# MCU.net
KiCad netlist of a schematic drawn in Altium Designer
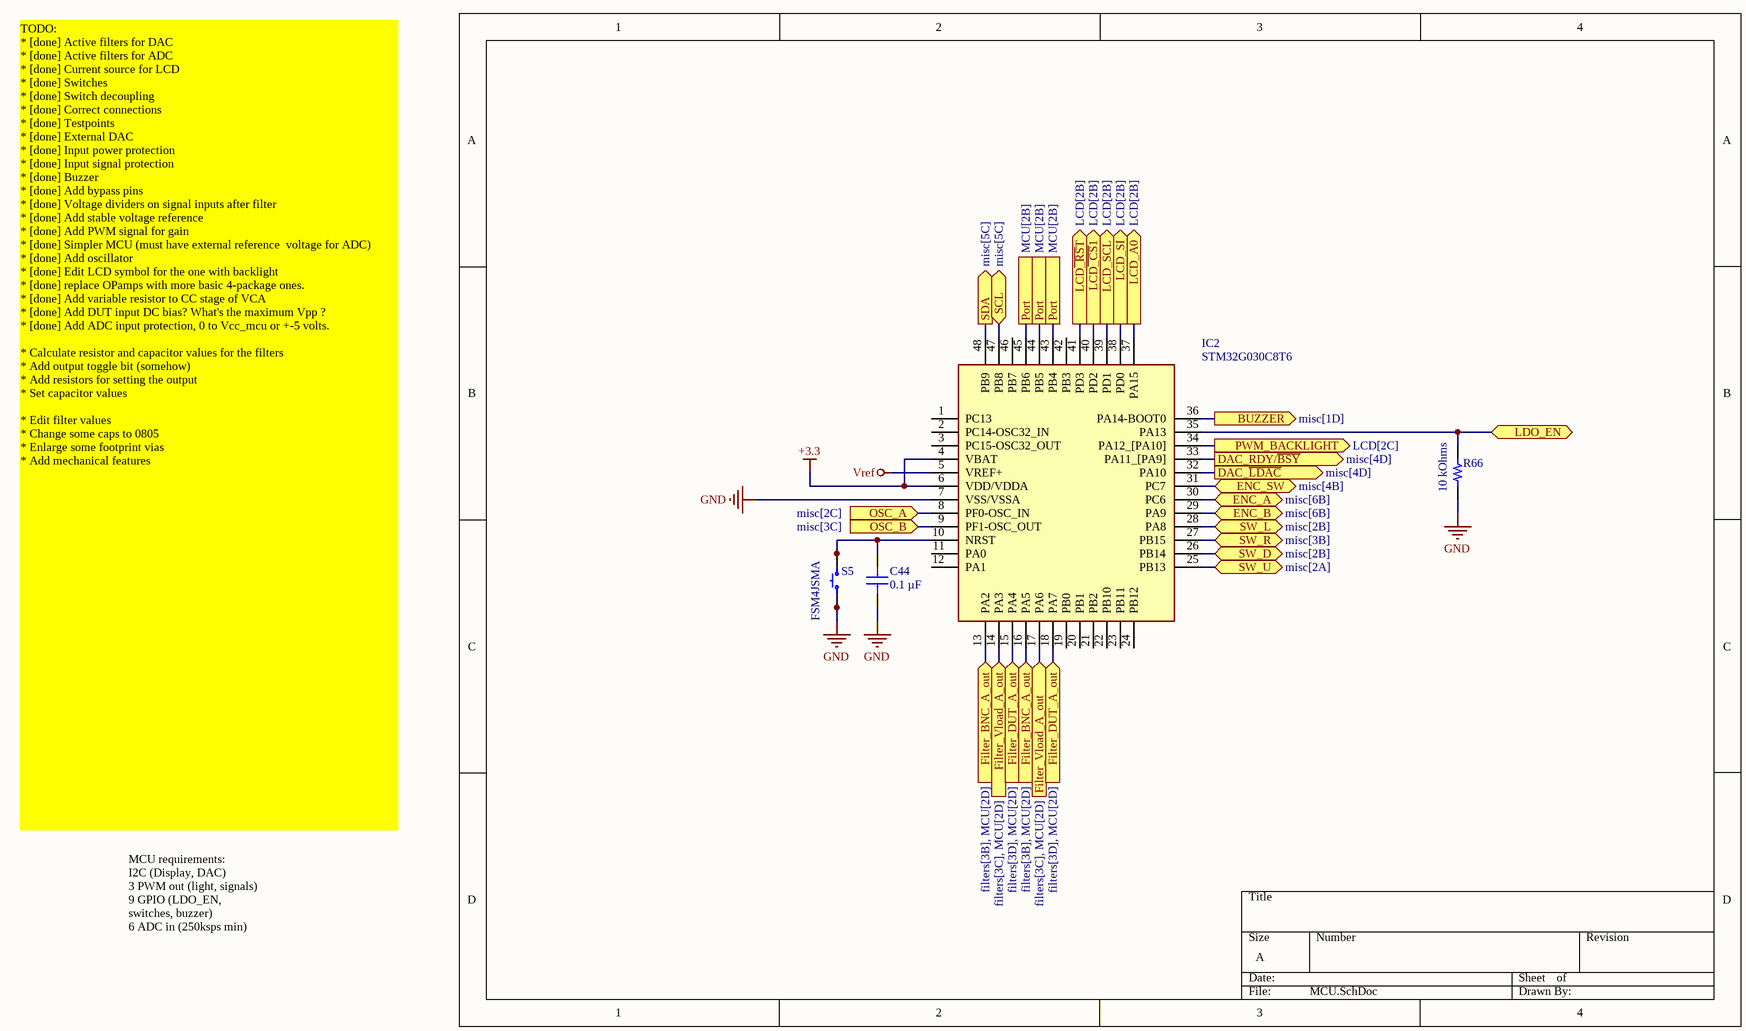
[diagram p0: MCU.SchDoc]

(export (version "E")
  (design (tool "Eeschema 10.0.6"))
  (components
    (comp (ref "C44")
      (value "0.1 µF")
      (footprint "CAP 1206_3216 - 0.8MM")
      (description "CAP CER 0.1UF 50V X7R 1206")
      (fields
        (field (name "PART NUMBER") "885012208087")
        (field (name "CAPACITANCE") "0.1 µF")
        (field (name "MANUFACTURER") "Würth Elektronik")
      )
      (libsource (lib "Celestial Altium Library - altium_library") (part "Capacitor"))
    )
    (comp (ref "IC2")
      (value "STM32G030C8T6")
      (footprint "QFP50P900X900X160-48N")
      (description "Integrated Circuit")
      (fields (field (name "MOUSER PART NUMBER") "511-STM32G030C8T6"))
      (libsource (lib "za_koncar") (part "STM32G030C8T6"))
    )
    (comp (ref "R66")
      (value "10 kOhms")
      (footprint "YAGEO RES 1206_3216")
      (description "RES SMD 10K OHM 1% 1/4W 1206")
      (fields (field (name "PART NUMBER") "RT1206FRE0710KL") (field (name "MANUFACTURER") "Yageo"))
      (libsource (lib "Celestial Altium Library - altium_library") (part "Resistor"))
    )
    (comp (ref "S5")
      (value "FSM4JSMA")
      (footprint "TE FSM4JSMA")
      (description "SWITCH TACTILE SPST-NO 0.05A 24V")
      (fields (field (name "MANUFACTURER") "TE Connectivity ALCOSWITCH Switches"))
      (libsource (lib "Celestial Altium Library - altium_library") (part "SPST-NO 4 PIN"))
    )
  )
  (nets
    (net (code "1") (name "+3.3") (class "Default")
      (node (ref "IC2") (pin "4") (pinfunction "VBAT_4") (pintype "passive"))
      (node (ref "IC2") (pin "6") (pinfunction "VDD/VDDA_6") (pintype "passive"))
    )
    (net (code "2") (name "/BUZZER") (class "Default")
      (node (ref "IC2") (pin "36") (pinfunction "PA14-BOOT0_36") (pintype "passive"))
    )
    (net (code "3") (name "/DAC_RDY{slash}~{BSY}") (class "Default")
      (node (ref "IC2") (pin "33") (pinfunction "PA11_[PA9]_33") (pintype "passive"))
    )
    (net (code "4") (name "/DAC_~{LDAC}") (class "Default")
      (node (ref "IC2") (pin "32") (pinfunction "PA10_32") (pintype "passive"))
    )
    (net (code "5") (name "/ENC_A") (class "Default")
      (node (ref "IC2") (pin "30") (pinfunction "PC6_30") (pintype "passive"))
    )
    (net (code "6") (name "/ENC_B") (class "Default")
      (node (ref "IC2") (pin "29") (pinfunction "PA9_29") (pintype "passive"))
    )
    (net (code "7") (name "/ENC_SW") (class "Default")
      (node (ref "IC2") (pin "31") (pinfunction "PC7_31") (pintype "passive"))
    )
    (net (code "8") (name "/Filter_BNC_A_out") (class "Default")
      (node (ref "IC2") (pin "13") (pinfunction "PA2_13") (pintype "passive"))
      (node (ref "IC2") (pin "16") (pinfunction "PA5_16") (pintype "passive"))
    )
    (net (code "9") (name "/Filter_DUT_A_out") (class "Default")
      (node (ref "IC2") (pin "15") (pinfunction "PA4_15") (pintype "passive"))
      (node (ref "IC2") (pin "18") (pinfunction "PA7_18") (pintype "passive"))
    )
    (net (code "10") (name "/Filter_Vload_A_out") (class "Default")
      (node (ref "IC2") (pin "14") (pinfunction "PA3_14") (pintype "passive"))
      (node (ref "IC2") (pin "17") (pinfunction "PA6_17") (pintype "passive"))
    )
    (net (code "11") (name "/LCD_A0") (class "Default")
      (node (ref "IC2") (pin "37") (pinfunction "PA15_37") (pintype "passive"))
    )
    (net (code "12") (name "/LCD_SCL") (class "Default")
      (node (ref "IC2") (pin "39") (pinfunction "PD1_39") (pintype "passive"))
    )
    (net (code "13") (name "/LCD_SI") (class "Default")
      (node (ref "IC2") (pin "38") (pinfunction "PD0_38") (pintype "passive"))
    )
    (net (code "14") (name "/LCD~{_CS}1") (class "Default")
      (node (ref "IC2") (pin "40") (pinfunction "PD2_40") (pintype "passive"))
    )
    (net (code "15") (name "/LCD~{_RS}T") (class "Default")
      (node (ref "IC2") (pin "41") (pinfunction "PD3_41") (pintype "passive"))
    )
    (net (code "16") (name "/LDO_EN") (class "Default")
      (node (ref "IC2") (pin "35") (pinfunction "PA13_35") (pintype "passive"))
      (node (ref "R66") (pin "1") (pinfunction "1_1") (pintype "passive"))
    )
    (net (code "17") (name "/OSC_A") (class "Default")
      (node (ref "IC2") (pin "8") (pinfunction "PF0-OSC_IN_8") (pintype "passive"))
    )
    (net (code "18") (name "/OSC_B") (class "Default")
      (node (ref "IC2") (pin "9") (pinfunction "PF1-OSC_OUT_9") (pintype "passive"))
    )
    (net (code "19") (name "/PWM_BACKLIGHT") (class "Default")
      (node (ref "IC2") (pin "34") (pinfunction "PA12_[PA10]_34") (pintype "passive"))
    )
    (net (code "20") (name "/Port") (class "Default")
      (node (ref "IC2") (pin "43") (pinfunction "PB4_43") (pintype "passive"))
      (node (ref "IC2") (pin "44") (pinfunction "PB5_44") (pintype "passive"))
      (node (ref "IC2") (pin "45") (pinfunction "PB6_45") (pintype "passive"))
    )
    (net (code "21") (name "/SCL") (class "Default")
      (node (ref "IC2") (pin "47") (pinfunction "PB8_47") (pintype "passive"))
    )
    (net (code "22") (name "/SDA") (class "Default")
      (node (ref "IC2") (pin "48") (pinfunction "PB9_48") (pintype "passive"))
    )
    (net (code "23") (name "/SW_D") (class "Default")
      (node (ref "IC2") (pin "26") (pinfunction "PB14_26") (pintype "passive"))
    )
    (net (code "24") (name "/SW_L") (class "Default")
      (node (ref "IC2") (pin "28") (pinfunction "PA8_28") (pintype "passive"))
    )
    (net (code "25") (name "/SW_R") (class "Default")
      (node (ref "IC2") (pin "27") (pinfunction "PB15_27") (pintype "passive"))
    )
    (net (code "26") (name "/SW_U") (class "Default")
      (node (ref "IC2") (pin "25") (pinfunction "PB13_25") (pintype "passive"))
    )
    (net (code "27") (name "GND") (class "Default")
      (node (ref "C44") (pin "1") (pinfunction "1_1") (pintype "passive"))
      (node (ref "IC2") (pin "7") (pinfunction "VSS/VSSA_7") (pintype "passive"))
      (node (ref "R66") (pin "2") (pinfunction "2_2") (pintype "passive"))
      (node (ref "S5") (pin "1") (pinfunction "1_1") (pintype "passive"))
      (node (ref "S5") (pin "2") (pinfunction "2_2") (pintype "passive"))
    )
    (net (code "28") (name "Net-(IC2-NRST)") (class "Default")
      (node (ref "C44") (pin "2") (pinfunction "2_2") (pintype "passive"))
      (node (ref "IC2") (pin "10") (pinfunction "NRST_10") (pintype "passive"))
      (node (ref "S5") (pin "3") (pinfunction "3_3") (pintype "passive"))
      (node (ref "S5") (pin "4") (pinfunction "4_4") (pintype "passive"))
    )
    (net (code "29") (name "Vref") (class "Default")
      (node (ref "IC2") (pin "5") (pinfunction "VREF+_5") (pintype "passive"))
    )
    (net (code "30") (name "unconnected-(IC2-PA0-Pad11)") (class "Default")
      (node (ref "IC2") (pin "11") (pinfunction "PA0_11") (pintype "passive"))
    )
    (net (code "31") (name "unconnected-(IC2-PA1-Pad12)") (class "Default")
      (node (ref "IC2") (pin "12") (pinfunction "PA1_12") (pintype "passive"))
    )
    (net (code "32") (name "unconnected-(IC2-PB0-Pad19)") (class "Default")
      (node (ref "IC2") (pin "19") (pinfunction "PB0_19") (pintype "passive"))
    )
    (net (code "33") (name "unconnected-(IC2-PB1-Pad20)") (class "Default")
      (node (ref "IC2") (pin "20") (pinfunction "PB1_20") (pintype "passive"))
    )
    (net (code "34") (name "unconnected-(IC2-PB2-Pad21)") (class "Default")
      (node (ref "IC2") (pin "21") (pinfunction "PB2_21") (pintype "passive"))
    )
    (net (code "35") (name "unconnected-(IC2-PB3-Pad42)") (class "Default")
      (node (ref "IC2") (pin "42") (pinfunction "PB3_42") (pintype "passive"))
    )
    (net (code "36") (name "unconnected-(IC2-PB7-Pad46)") (class "Default")
      (node (ref "IC2") (pin "46") (pinfunction "PB7_46") (pintype "passive"))
    )
    (net (code "37") (name "unconnected-(IC2-PB10-Pad22)") (class "Default")
      (node (ref "IC2") (pin "22") (pinfunction "PB10_22") (pintype "passive"))
    )
    (net (code "38") (name "unconnected-(IC2-PB11-Pad23)") (class "Default")
      (node (ref "IC2") (pin "23") (pinfunction "PB11_23") (pintype "passive"))
    )
    (net (code "39") (name "unconnected-(IC2-PB12-Pad24)") (class "Default")
      (node (ref "IC2") (pin "24") (pinfunction "PB12_24") (pintype "passive"))
    )
    (net (code "40") (name "unconnected-(IC2-PC13-Pad1)") (class "Default")
      (node (ref "IC2") (pin "1") (pinfunction "PC13_1") (pintype "passive"))
    )
    (net (code "41") (name "unconnected-(IC2-PC14-OSC32_IN-Pad2)") (class "Default")
      (node (ref "IC2") (pin "2") (pinfunction "PC14-OSC32_IN_2") (pintype "passive"))
    )
    (net (code "42") (name "unconnected-(IC2-PC15-OSC32_OUT-Pad3)") (class "Default")
      (node (ref "IC2") (pin "3") (pinfunction "PC15-OSC32_OUT_3") (pintype "passive"))
    )
  )
)
